# Power_5V-8A_CurLim.net
KiCad netlist of a schematic drawn in EAGLE
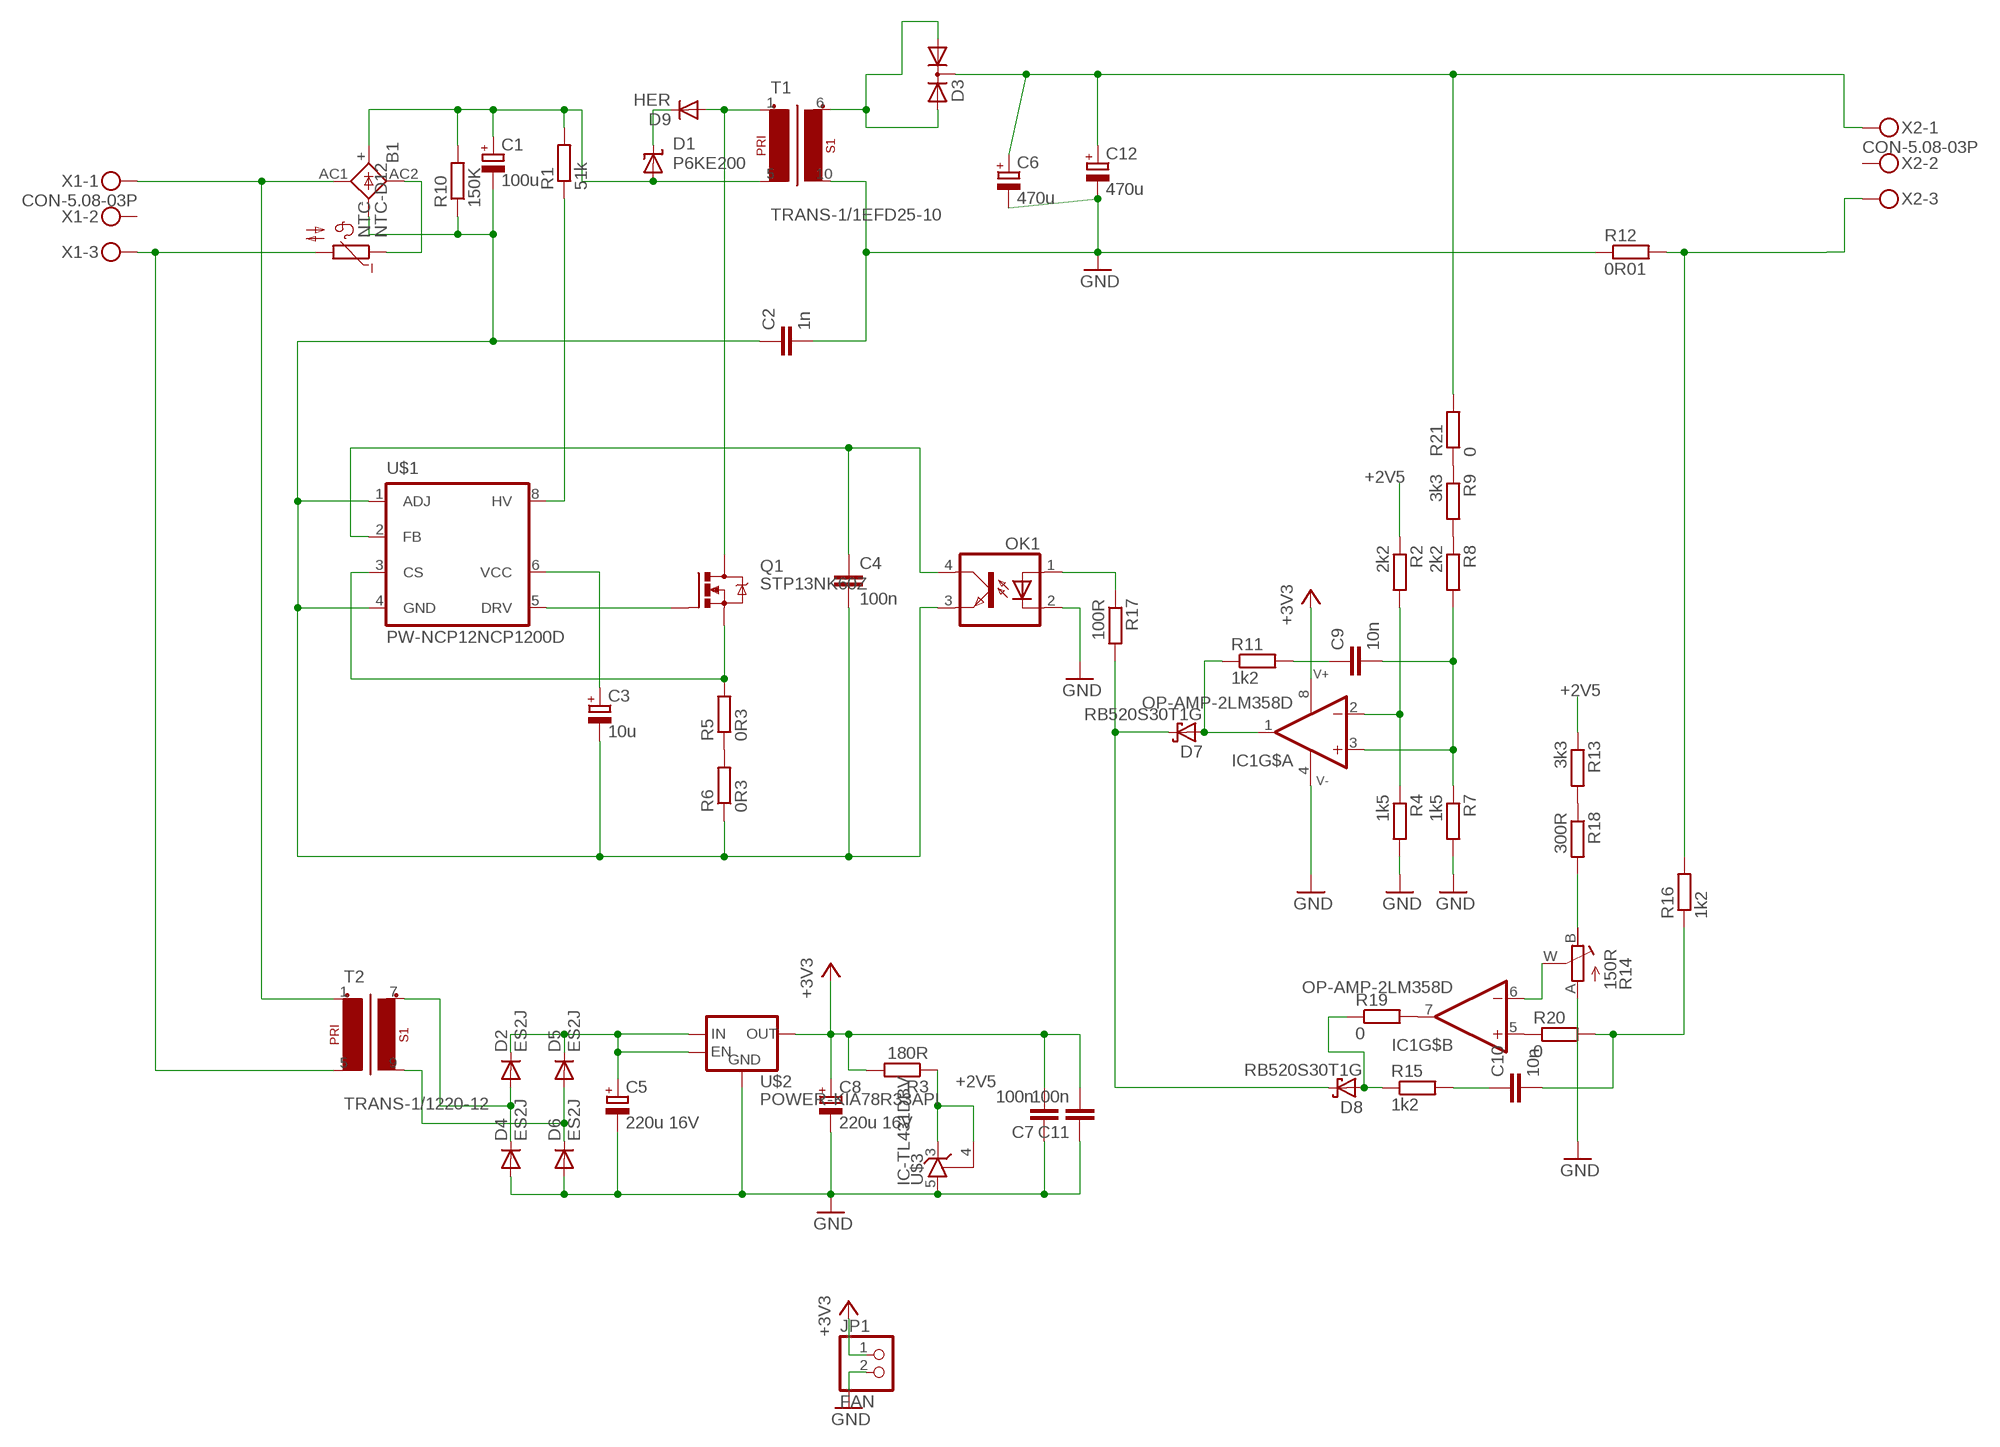
[diagram p0: schematic, sheet 1]

(export (version "E")
  (design (tool "Eeschema 10.0.6"))
  (components
    (comp (ref "B1")
      (value "RECTIFIERKBL")
      (footprint "eagle-import:KBL")
      (libsource (lib "eagle-import") (part "RECTIFIERKBL"))
    )
    (comp (ref "C1")
      (value "100u")
      (footprint "eagle-import:C_D25-G10-CLAMP")
      (libsource (lib "eagle-import") (part "CAP-POL_E25-10-C"))
    )
    (comp (ref "C2")
      (value "1n")
      (footprint "eagle-import:C050-024X044")
      (libsource (lib "eagle-import") (part "CAP_C50-024X044"))
    )
    (comp (ref "C3")
      (value "10u")
      (footprint "eagle-import:E5-5")
      (libsource (lib "eagle-import") (part "CAP-POL_E5-5"))
    )
    (comp (ref "C4")
      (value "100n")
      (footprint "eagle-import:C0805")
      (libsource (lib "eagle-import") (part "CAP_0805"))
    )
    (comp (ref "C5")
      (value "220u 16V")
      (footprint "eagle-import:E3,5-8")
      (libsource (lib "eagle-import") (part "CAP-POL_E3.5-8"))
    )
    (comp (ref "C6")
      (value "470u")
      (footprint "eagle-import:E5-10,5")
      (libsource (lib "eagle-import") (part "CAP-POL_E5-10.5"))
    )
    (comp (ref "C7")
      (value "100n")
      (footprint "eagle-import:C0805")
      (libsource (lib "eagle-import") (part "CAP_0805"))
    )
    (comp (ref "C8")
      (value "220u 16V")
      (footprint "eagle-import:E3,5-8")
      (libsource (lib "eagle-import") (part "CAP-POL_E3.5-8"))
    )
    (comp (ref "C9")
      (value "10n")
      (footprint "eagle-import:C1206")
      (libsource (lib "eagle-import") (part "CAP_1206"))
    )
    (comp (ref "C10")
      (value "10n")
      (footprint "eagle-import:C1206")
      (libsource (lib "eagle-import") (part "CAP_1206"))
    )
    (comp (ref "C11")
      (value "100n")
      (footprint "eagle-import:C0805")
      (libsource (lib "eagle-import") (part "CAP_0805"))
    )
    (comp (ref "C12")
      (value "470u")
      (footprint "eagle-import:E5-10,5")
      (libsource (lib "eagle-import") (part "CAP-POL_E5-10.5"))
    )
    (comp (ref "D1")
      (value "P6KE200")
      (footprint "eagle-import:DO15-12")
      (libsource (lib "eagle-import") (part "SUPRESSORDO-204AC"))
    )
    (comp (ref "D2")
      (value "ES2J")
      (footprint "eagle-import:DO214AC")
      (libsource (lib "eagle-import") (part "DIODE_ES1J"))
    )
    (comp (ref "D3")
      (value "DIODE-DUAL-CCTO-220V")
      (footprint "eagle-import:TO-220V")
      (libsource (lib "eagle-import") (part "DIODE-DUAL-CCTO-220V"))
    )
    (comp (ref "D4")
      (value "ES2J")
      (footprint "eagle-import:DO214AC")
      (libsource (lib "eagle-import") (part "DIODE_ES1J"))
    )
    (comp (ref "D5")
      (value "ES2J")
      (footprint "eagle-import:DO214AC")
      (libsource (lib "eagle-import") (part "DIODE_ES1J"))
    )
    (comp (ref "D6")
      (value "ES2J")
      (footprint "eagle-import:DO214AC")
      (libsource (lib "eagle-import") (part "DIODE_ES1J"))
    )
    (comp (ref "D7")
      (value "RB520S30T1G")
      (footprint "eagle-import:SOD523")
      (libsource (lib "eagle-import") (part "DIODE-SH_SOD523"))
    )
    (comp (ref "D8")
      (value "RB520S30T1G")
      (footprint "eagle-import:SOD523")
      (libsource (lib "eagle-import") (part "DIODE-SH_SOD523"))
    )
    (comp (ref "D9")
      (value "HER")
      (footprint "eagle-import:DO201-15")
      (libsource (lib "eagle-import") (part "DIODE_DO-201"))
    )
    (comp (ref "IC1")
      (value "OP-AMP-2LM358D")
      (footprint "eagle-import:SO8")
      (libsource (lib "eagle-import") (part "OP-AMP-2LM358D"))
    )
    (comp (ref "JP1")
      (value "FAN")
      (footprint "eagle-import:1X02")
      (libsource (lib "eagle-import") (part "PINHD-1X2"))
    )
    (comp (ref "NTC")
      (value "NTC-D12")
      (footprint "eagle-import:NTC-D12")
      (libsource (lib "eagle-import") (part "NTC-D12"))
    )
    (comp (ref "OK1")
      (value "OPTOTRANSPC817")
      (footprint "eagle-import:DIL04")
      (fields (field (name "MPN") "PC817X4J000F"))
      (libsource (lib "eagle-import") (part "OPTOTRANSPC817"))
    )
    (comp (ref "Q1")
      (value "STP13NK60Z")
      (footprint "eagle-import:TO-220V")
      (libsource (lib "eagle-import") (part "FET-NTO-220"))
    )
    (comp (ref "R1")
      (value "51k")
      (footprint "eagle-import:SQP-5")
      (libsource (lib "eagle-import") (part "R_SQP-5"))
    )
    (comp (ref "R2")
      (value "2k2")
      (footprint "eagle-import:R1206")
      (libsource (lib "eagle-import") (part "R_1206"))
    )
    (comp (ref "R3")
      (value "180R")
      (footprint "eagle-import:R1206")
      (libsource (lib "eagle-import") (part "R_1206"))
    )
    (comp (ref "R4")
      (value "1k5")
      (footprint "eagle-import:R1206")
      (libsource (lib "eagle-import") (part "R_1206"))
    )
    (comp (ref "R5")
      (value "0R3")
      (footprint "eagle-import:KNP-100B")
      (libsource (lib "eagle-import") (part "R_KNP-100B"))
    )
    (comp (ref "R6")
      (value "0R3")
      (footprint "eagle-import:KNP-100B")
      (libsource (lib "eagle-import") (part "R_KNP-100B"))
    )
    (comp (ref "R7")
      (value "1k5")
      (footprint "eagle-import:R1206")
      (libsource (lib "eagle-import") (part "R_1206"))
    )
    (comp (ref "R8")
      (value "2k2")
      (footprint "eagle-import:R1206")
      (libsource (lib "eagle-import") (part "R_1206"))
    )
    (comp (ref "R9")
      (value "3k3")
      (footprint "eagle-import:R1206")
      (libsource (lib "eagle-import") (part "R_1206"))
    )
    (comp (ref "R10")
      (value "150K")
      (footprint "eagle-import:MF-0125")
      (libsource (lib "eagle-import") (part "R_MF-0125"))
    )
    (comp (ref "R11")
      (value "1k2")
      (footprint "eagle-import:R1206")
      (libsource (lib "eagle-import") (part "R_1206"))
    )
    (comp (ref "R12")
      (value "0R01")
      (footprint "eagle-import:R2512")
      (libsource (lib "eagle-import") (part "R_2512"))
    )
    (comp (ref "R13")
      (value "3k3")
      (footprint "eagle-import:R1206")
      (libsource (lib "eagle-import") (part "R_1206"))
    )
    (comp (ref "R14")
      (value "150R")
      (footprint "eagle-import:RJ9W")
      (libsource (lib "eagle-import") (part "R_POTTURN-X"))
    )
    (comp (ref "R15")
      (value "1k2")
      (footprint "eagle-import:R1206")
      (libsource (lib "eagle-import") (part "R_1206"))
    )
    (comp (ref "R16")
      (value "1k2")
      (footprint "eagle-import:R1206")
      (libsource (lib "eagle-import") (part "R_1206"))
    )
    (comp (ref "R17")
      (value "100R")
      (footprint "eagle-import:R1206")
      (libsource (lib "eagle-import") (part "R_1206"))
    )
    (comp (ref "R18")
      (value "300R")
      (footprint "eagle-import:R1206")
      (libsource (lib "eagle-import") (part "R_1206"))
    )
    (comp (ref "R19")
      (value "0")
      (footprint "eagle-import:R0805")
      (libsource (lib "eagle-import") (part "R_0805"))
    )
    (comp (ref "R20")
      (value "0")
      (footprint "eagle-import:R0805")
      (libsource (lib "eagle-import") (part "R_0805"))
    )
    (comp (ref "R21")
      (value "0")
      (footprint "eagle-import:R0805")
      (libsource (lib "eagle-import") (part "R_0805"))
    )
    (comp (ref "T1")
      (value "TRANS-1/1EFD25-10")
      (footprint "eagle-import:EFD25_10PIN")
      (libsource (lib "eagle-import") (part "TRANS-1/1EFD25-10"))
    )
    (comp (ref "T2")
      (value "TRANS-1/1220-12")
      (footprint "eagle-import:32.5-27.5-27.5")
      (libsource (lib "eagle-import") (part "TRANS-1/1220-12"))
    )
    (comp (ref "U$1")
      (value "PW-NCP12NCP1200D")
      (footprint "eagle-import:SO8")
      (libsource (lib "eagle-import") (part "PW-NCP12NCP1200D"))
    )
    (comp (ref "U$2")
      (value "POWER-KIA78R33API")
      (footprint "eagle-import:TO-220_4")
      (libsource (lib "eagle-import") (part "POWER-KIA78R33API"))
    )
    (comp (ref "U$3")
      (value "IC-TL431DBV")
      (footprint "eagle-import:SOT23-5L")
      (libsource (lib "eagle-import") (part "IC-TL431DBV"))
    )
    (comp (ref "X1")
      (value "CON-5.08-03P")
      (footprint "eagle-import:MKDSN1,5_3-5,08")
      (libsource (lib "eagle-import") (part "CON-5.08-03P"))
    )
    (comp (ref "X2")
      (value "CON-5.08-03P")
      (footprint "eagle-import:MKDSN1,5_3-5,08")
      (libsource (lib "eagle-import") (part "CON-5.08-03P"))
    )
  )
  (nets
    (net (code "1") (name "+3V3") (class "Default")
      (node (ref "C11") (pin "2") (pinfunction "2_2") (pintype "passive"))
      (node (ref "C7") (pin "2") (pinfunction "2_2") (pintype "passive"))
      (node (ref "C8") (pin "+") (pinfunction "+_+") (pintype "passive"))
      (node (ref "IC1") (pin "8") (pinfunction "V+_8") (pintype "power_in"))
      (node (ref "JP1") (pin "1") (pinfunction "1_1") (pintype "passive"))
      (node (ref "R3") (pin "2") (pinfunction "2_2") (pintype "passive"))
      (node (ref "U$2") (pin "O") (pinfunction "OUT_O") (pintype "passive"))
    )
    (net (code "2") (name "/+2V5") (class "Default")
      (node (ref "R13") (pin "1") (pinfunction "1_1") (pintype "passive"))
      (node (ref "R2") (pin "1") (pinfunction "1_1") (pintype "passive"))
      (node (ref "R3") (pin "1") (pinfunction "1_1") (pintype "passive"))
      (node (ref "U$3") (pin "3") (pinfunction "C_3") (pintype "passive"))
      (node (ref "U$3") (pin "4") (pinfunction "R_4") (pintype "passive"))
    )
    (net (code "3") (name "GND") (class "Default")
      (node (ref "C11") (pin "1") (pinfunction "1_1") (pintype "passive"))
      (node (ref "C12") (pin "-") (pinfunction "-_-") (pintype "passive"))
      (node (ref "C2") (pin "2") (pinfunction "2_2") (pintype "passive"))
      (node (ref "C5") (pin "-") (pinfunction "-_-") (pintype "passive"))
      (node (ref "C6") (pin "-") (pinfunction "-_-") (pintype "passive"))
      (node (ref "C7") (pin "1") (pinfunction "1_1") (pintype "passive"))
      (node (ref "C8") (pin "-") (pinfunction "-_-") (pintype "passive"))
      (node (ref "D4") (pin "A") (pinfunction "A_A") (pintype "passive"))
      (node (ref "D6") (pin "A") (pinfunction "A_A") (pintype "passive"))
      (node (ref "IC1") (pin "4") (pinfunction "V-_4") (pintype "power_in"))
      (node (ref "JP1") (pin "2") (pinfunction "2_2") (pintype "passive"))
      (node (ref "OK1") (pin "2") (pinfunction "C_2") (pintype "passive"))
      (node (ref "R12") (pin "1") (pinfunction "1_1") (pintype "passive"))
      (node (ref "R14") (pin "A") (pinfunction "A_A") (pintype "passive"))
      (node (ref "R4") (pin "2") (pinfunction "2_2") (pintype "passive"))
      (node (ref "R7") (pin "2") (pinfunction "2_2") (pintype "passive"))
      (node (ref "T1") (pin "10") (pinfunction "S1-2_10") (pintype "passive"))
      (node (ref "U$2") (pin "G") (pinfunction "GND_G") (pintype "input"))
      (node (ref "U$3") (pin "5") (pinfunction "A_5") (pintype "passive"))
    )
    (net (code "4") (name "Net-(B1-AC1)") (class "Default")
      (node (ref "B1") (pin "AC2") (pinfunction "AC1_AC2") (pintype "passive"))
      (node (ref "NTC") (pin "1") (pinfunction "1_1") (pintype "passive"))
    )
    (net (code "5") (name "Net-(B1-AC2)") (class "Default")
      (node (ref "B1") (pin "AC1") (pinfunction "AC2_AC1") (pintype "passive"))
      (node (ref "T2") (pin "1") (pinfunction "P1-1_1") (pintype "passive"))
      (node (ref "X1") (pin "1") (pinfunction "KL_1") (pintype "passive"))
    )
    (net (code "6") (name "Net-(C9-Pad1)") (class "Default")
      (node (ref "C9") (pin "1") (pinfunction "1_1") (pintype "passive"))
      (node (ref "R11") (pin "2") (pinfunction "2_2") (pintype "passive"))
    )
    (net (code "7") (name "Net-(C10-Pad1)") (class "Default")
      (node (ref "C10") (pin "1") (pinfunction "1_1") (pintype "passive"))
      (node (ref "R15") (pin "2") (pinfunction "2_2") (pintype "passive"))
    )
    (net (code "8") (name "Net-(C10-Pad2)") (class "Default")
      (node (ref "C10") (pin "2") (pinfunction "2_2") (pintype "passive"))
      (node (ref "R16") (pin "1") (pinfunction "1_1") (pintype "passive"))
      (node (ref "R20") (pin "2") (pinfunction "2_2") (pintype "passive"))
    )
    (net (code "9") (name "Net-(D1-PadC)") (class "Default")
      (node (ref "D1") (pin "C") (pinfunction "C_C") (pintype "passive"))
      (node (ref "D9") (pin "C") (pinfunction "C_C") (pintype "passive"))
    )
    (net (code "10") (name "Net-(D3-A1)") (class "Default")
      (node (ref "D3") (pin "1") (pinfunction "A1_1") (pintype "passive"))
      (node (ref "D3") (pin "3") (pinfunction "A2_3") (pintype "passive"))
      (node (ref "T1") (pin "6") (pinfunction "S1-1_6") (pintype "passive"))
    )
    (net (code "11") (name "Net-(D3-C)") (class "Default")
      (node (ref "C12") (pin "+") (pinfunction "+_+") (pintype "passive"))
      (node (ref "C6") (pin "+") (pinfunction "+_+") (pintype "passive"))
      (node (ref "D3") (pin "2") (pinfunction "C_2") (pintype "passive"))
      (node (ref "R21") (pin "2") (pinfunction "2_2") (pintype "passive"))
      (node (ref "X2") (pin "1") (pinfunction "KL_1") (pintype "passive"))
    )
    (net (code "12") (name "Net-(D7-PadC)") (class "Default")
      (node (ref "D7") (pin "C") (pinfunction "C_C") (pintype "passive"))
      (node (ref "D8") (pin "C") (pinfunction "C_C") (pintype "passive"))
      (node (ref "R17") (pin "2") (pinfunction "2_2") (pintype "passive"))
    )
    (net (code "13") (name "Net-(D8-PadA)") (class "Default")
      (node (ref "D8") (pin "A") (pinfunction "A_A") (pintype "passive"))
      (node (ref "R15") (pin "1") (pinfunction "1_1") (pintype "passive"))
      (node (ref "R19") (pin "1") (pinfunction "1_1") (pintype "passive"))
    )
    (net (code "14") (name "Net-(IC1A-+IN)") (class "Default")
      (node (ref "C9") (pin "2") (pinfunction "2_2") (pintype "passive"))
      (node (ref "IC1") (pin "3") (pinfunction "+IN_3") (pintype "input"))
      (node (ref "R7") (pin "1") (pinfunction "1_1") (pintype "passive"))
      (node (ref "R8") (pin "2") (pinfunction "2_2") (pintype "passive"))
    )
    (net (code "15") (name "Net-(IC1A--IN)") (class "Default")
      (node (ref "IC1") (pin "2") (pinfunction "-IN_2") (pintype "input"))
      (node (ref "R2") (pin "2") (pinfunction "2_2") (pintype "passive"))
      (node (ref "R4") (pin "1") (pinfunction "1_1") (pintype "passive"))
    )
    (net (code "16") (name "Net-(IC1A-OUT)") (class "Default")
      (node (ref "D7") (pin "A") (pinfunction "A_A") (pintype "passive"))
      (node (ref "IC1") (pin "1") (pinfunction "OUT_1") (pintype "output"))
      (node (ref "R11") (pin "1") (pinfunction "1_1") (pintype "passive"))
    )
    (net (code "17") (name "Net-(IC1B-+IN)") (class "Default")
      (node (ref "IC1") (pin "5") (pinfunction "+IN_5") (pintype "input"))
      (node (ref "R20") (pin "1") (pinfunction "1_1") (pintype "passive"))
    )
    (net (code "18") (name "Net-(IC1B--IN)") (class "Default")
      (node (ref "IC1") (pin "6") (pinfunction "-IN_6") (pintype "input"))
      (node (ref "R14") (pin "W") (pinfunction "S_W") (pintype "passive"))
    )
    (net (code "19") (name "Net-(IC1B-OUT)") (class "Default")
      (node (ref "IC1") (pin "7") (pinfunction "OUT_7") (pintype "output"))
      (node (ref "R19") (pin "2") (pinfunction "2_2") (pintype "passive"))
    )
    (net (code "20") (name "Net-(OK1-A)") (class "Default")
      (node (ref "OK1") (pin "1") (pinfunction "A_1") (pintype "passive"))
      (node (ref "R17") (pin "1") (pinfunction "1_1") (pintype "passive"))
    )
    (net (code "21") (name "Net-(OK1-COL)") (class "Default")
      (node (ref "C4") (pin "1") (pinfunction "1_1") (pintype "passive"))
      (node (ref "OK1") (pin "4") (pinfunction "COL_4") (pintype "passive"))
      (node (ref "U$1") (pin "2") (pinfunction "FB_2") (pintype "input"))
    )
    (net (code "22") (name "Net-(OK1-EMIT)") (class "Default")
      (node (ref "B1") (pin "-") (pinfunction "-_-") (pintype "passive"))
      (node (ref "C1") (pin "-") (pinfunction "-_-") (pintype "passive"))
      (node (ref "C2") (pin "1") (pinfunction "1_1") (pintype "passive"))
      (node (ref "C3") (pin "-") (pinfunction "-_-") (pintype "passive"))
      (node (ref "C4") (pin "2") (pinfunction "2_2") (pintype "passive"))
      (node (ref "OK1") (pin "3") (pinfunction "EMIT_3") (pintype "passive"))
      (node (ref "R10") (pin "1") (pinfunction "1_1") (pintype "passive"))
      (node (ref "R6") (pin "1") (pinfunction "1_1") (pintype "passive"))
      (node (ref "U$1") (pin "1") (pinfunction "ADJ_1") (pintype "passive"))
      (node (ref "U$1") (pin "4") (pinfunction "GND_4") (pintype "passive"))
    )
    (net (code "23") (name "Net-(Q1-D)") (class "Default")
      (node (ref "D9") (pin "A") (pinfunction "A_A") (pintype "passive"))
      (node (ref "Q1") (pin "2") (pinfunction "D_2") (pintype "passive"))
      (node (ref "T1") (pin "1") (pinfunction "P1-1_1") (pintype "passive"))
    )
    (net (code "24") (name "Net-(Q1-G)") (class "Default")
      (node (ref "Q1") (pin "1") (pinfunction "G_1") (pintype "passive"))
      (node (ref "U$1") (pin "5") (pinfunction "DRV_5") (pintype "power_in"))
    )
    (net (code "25") (name "Net-(Q1-S)") (class "Default")
      (node (ref "Q1") (pin "3") (pinfunction "S_3") (pintype "passive"))
      (node (ref "R5") (pin "2") (pinfunction "2_2") (pintype "passive"))
      (node (ref "U$1") (pin "3") (pinfunction "CS_3") (pintype "input"))
    )
    (net (code "26") (name "Net-(R5-Pad1)") (class "Default")
      (node (ref "R5") (pin "1") (pinfunction "1_1") (pintype "passive"))
      (node (ref "R6") (pin "2") (pinfunction "2_2") (pintype "passive"))
    )
    (net (code "27") (name "Net-(R8-Pad1)") (class "Default")
      (node (ref "R8") (pin "1") (pinfunction "1_1") (pintype "passive"))
      (node (ref "R9") (pin "2") (pinfunction "2_2") (pintype "passive"))
    )
    (net (code "28") (name "Net-(R13-Pad2)") (class "Default")
      (node (ref "R13") (pin "2") (pinfunction "2_2") (pintype "passive"))
      (node (ref "R18") (pin "1") (pinfunction "1_1") (pintype "passive"))
    )
    (net (code "29") (name "Net-(R14-E)") (class "Default")
      (node (ref "R14") (pin "B") (pinfunction "E_B") (pintype "passive"))
      (node (ref "R18") (pin "2") (pinfunction "2_2") (pintype "passive"))
    )
    (net (code "30") (name "Net-(R21-Pad1)") (class "Default")
      (node (ref "R21") (pin "1") (pinfunction "1_1") (pintype "passive"))
      (node (ref "R9") (pin "1") (pinfunction "1_1") (pintype "passive"))
    )
    (net (code "31") (name "Net-(T1-P1-2)") (class "Default")
      (node (ref "B1") (pin "+") (pinfunction "+_+") (pintype "passive"))
      (node (ref "C1") (pin "+") (pinfunction "+_+") (pintype "passive"))
      (node (ref "D1") (pin "A") (pinfunction "A_A") (pintype "passive"))
      (node (ref "R1") (pin "2") (pinfunction "2_2") (pintype "passive"))
      (node (ref "R10") (pin "2") (pinfunction "2_2") (pintype "passive"))
      (node (ref "T1") (pin "5") (pinfunction "P1-2_5") (pintype "passive"))
    )
    (net (code "32") (name "Net-(T2-P1-2)") (class "Default")
      (node (ref "NTC") (pin "2") (pinfunction "2_2") (pintype "passive"))
      (node (ref "T2") (pin "5") (pinfunction "P1-2_5") (pintype "passive"))
      (node (ref "X1") (pin "3") (pinfunction "KL_3") (pintype "passive"))
    )
    (net (code "33") (name "Net-(T2-S1-1)") (class "Default")
      (node (ref "D2") (pin "A") (pinfunction "A_A") (pintype "passive"))
      (node (ref "D4") (pin "C") (pinfunction "C_C") (pintype "passive"))
      (node (ref "T2") (pin "7") (pinfunction "S1-1_7") (pintype "passive"))
    )
    (net (code "34") (name "Net-(T2-S1-2)") (class "Default")
      (node (ref "D5") (pin "A") (pinfunction "A_A") (pintype "passive"))
      (node (ref "D6") (pin "C") (pinfunction "C_C") (pintype "passive"))
      (node (ref "T2") (pin "9") (pinfunction "S1-2_9") (pintype "passive"))
    )
    (net (code "35") (name "Net-(U$1-HV)") (class "Default")
      (node (ref "R1") (pin "1") (pinfunction "1_1") (pintype "passive"))
      (node (ref "U$1") (pin "8") (pinfunction "HV_8") (pintype "passive"))
    )
    (net (code "36") (name "Net-(U$1-VCC)") (class "Default")
      (node (ref "C3") (pin "+") (pinfunction "+_+") (pintype "passive"))
      (node (ref "U$1") (pin "6") (pinfunction "VCC_6") (pintype "output"))
    )
    (net (code "37") (name "Net-(U$2-EN)") (class "Default")
      (node (ref "C5") (pin "+") (pinfunction "+_+") (pintype "passive"))
      (node (ref "D2") (pin "C") (pinfunction "C_C") (pintype "passive"))
      (node (ref "D5") (pin "C") (pinfunction "C_C") (pintype "passive"))
      (node (ref "U$2") (pin "E") (pinfunction "EN_E") (pintype "input"))
      (node (ref "U$2") (pin "I") (pinfunction "IN_I") (pintype "input"))
    )
    (net (code "38") (name "Net-(X2C-KL)") (class "Default")
      (node (ref "R12") (pin "2") (pinfunction "2_2") (pintype "passive"))
      (node (ref "R16") (pin "2") (pinfunction "2_2") (pintype "passive"))
      (node (ref "X2") (pin "3") (pinfunction "KL_3") (pintype "passive"))
    )
    (net (code "39") (name "unconnected-(X1B-KL-Pad2)") (class "Default")
      (node (ref "X1") (pin "2") (pinfunction "KL_2") (pintype "passive"))
    )
    (net (code "40") (name "unconnected-(X2B-KL-Pad2)") (class "Default")
      (node (ref "X2") (pin "2") (pinfunction "KL_2") (pintype "passive"))
    )
  )
)
